# avr910_bluetooth.net
KiCad netlist of a schematic drawn in Altium Designer
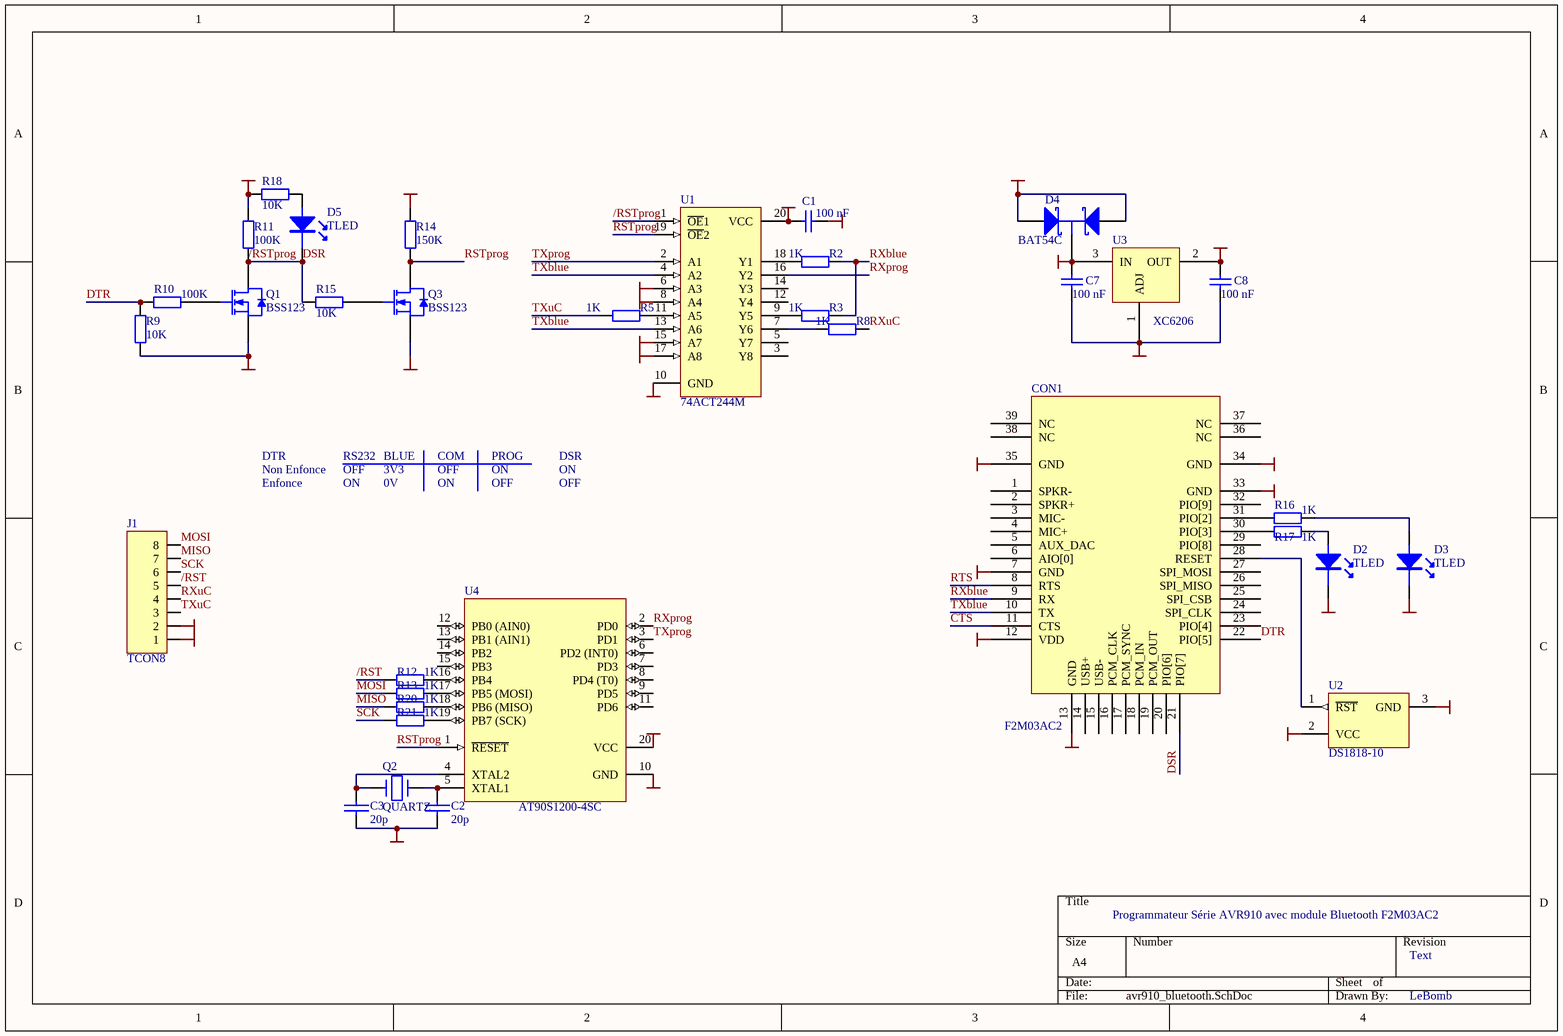
[diagram p0: avr910_bluetooth.SchDoc]

(export (version "E")
  (design (tool "Eeschema 10.0.6"))
  (components
    (comp (ref "C1")
      (value "100 nF")
      (footprint "0805")
      (description "Capacitor")
      (fields (field (name "Comment") "Cap") (field (name "PUBLISHER") "Altium Limited"))
      (libsource (lib "Miscellaneous Devices") (part "Cap"))
    )
    (comp (ref "C2") (value "20p") (footprint "0805") (libsource (lib "*") (part "CONDO")))
    (comp (ref "C3") (value "20p") (footprint "0805") (libsource (lib "*") (part "CONDO")))
    (comp (ref "C7")
      (value "100 nF")
      (footprint "0805")
      (description "Capacitor")
      (fields (field (name "Comment") "Cap") (field (name "PUBLISHER") "Altium Limited"))
      (libsource (lib "Miscellaneous Devices") (part "Cap"))
    )
    (comp (ref "C8")
      (value "100 nF")
      (footprint "0805")
      (description "Capacitor")
      (fields (field (name "Comment") "Cap") (field (name "PUBLISHER") "Altium Limited"))
      (libsource (lib "Miscellaneous Devices") (part "Cap"))
    )
    (comp (ref "CON1")
      (value "F2M03AC2")
      (footprint "F2M03AC2_conn")
      (libsource (lib "lebomb") (part "F2M03AC2"))
    )
    (comp (ref "D2") (value "TLED") (footprint "0805") (libsource (lib "ROB03") (part "TLED")))
    (comp (ref "D3") (value "TLED") (footprint "0805") (libsource (lib "ROB03") (part "TLED")))
    (comp (ref "D4")
      (value "BAT54C")
      (footprint "SOT23")
      (description "Schottky Barrier Double Diode")
      (fields (field (name "PUBLISHER") "Altium Limited"))
      (libsource (lib "Philips Discrete Diode - Schottky") (part "BAT54C"))
    )
    (comp (ref "D5") (value "TLED") (footprint "0805") (libsource (lib "ROB03") (part "TLED")))
    (comp (ref "J1") (value "TCON8") (footprint "TSIP8") (libsource (lib "ROB04") (part "TCON8")))
    (comp (ref "Q1")
      (value "BSS123")
      (footprint "SOT23")
      (description "N-channel Enhancement Mode Vertical D-MOSFET")
      (fields (field (name "PUBLISHER") "Altium Limited"))
      (libsource (lib "Philips Discrete MOSFET - Low Power") (part "BSS123"))
    )
    (comp (ref "Q2") (value "QUARTZ") (footprint "XTAL1") (libsource (lib "*") (part "QUARTZ")))
    (comp (ref "Q3")
      (value "BSS123")
      (footprint "SOT23")
      (description "N-channel Enhancement Mode Vertical D-MOSFET")
      (fields (field (name "PUBLISHER") "Altium Limited"))
      (libsource (lib "Philips Discrete MOSFET - Low Power") (part "BSS123"))
    )
    (comp (ref "R2")
      (value "1K")
      (footprint "0805")
      (description "Resistor")
      (fields (field (name "Comment") "Res2") (field (name "PUBLISHER") "Altium Limited"))
      (libsource (lib "Miscellaneous Devices") (part "Res2"))
    )
    (comp (ref "R3")
      (value "1K")
      (footprint "0805")
      (description "Resistor")
      (fields (field (name "Comment") "Res2") (field (name "PUBLISHER") "Altium Limited"))
      (libsource (lib "Miscellaneous Devices") (part "Res2"))
    )
    (comp (ref "R5")
      (value "1K")
      (footprint "0805")
      (description "Resistor")
      (fields (field (name "Comment") "Res2") (field (name "PUBLISHER") "Altium Limited"))
      (libsource (lib "Miscellaneous Devices") (part "Res2"))
    )
    (comp (ref "R8")
      (value "1K")
      (footprint "0805")
      (description "Resistor")
      (fields (field (name "Comment") "Res2") (field (name "PUBLISHER") "Altium Limited"))
      (libsource (lib "Miscellaneous Devices") (part "Res2"))
    )
    (comp (ref "R9")
      (value "10K")
      (footprint "0805")
      (description "Resistor")
      (fields (field (name "Comment") "Res2") (field (name "PUBLISHER") "Altium Limited"))
      (libsource (lib "") (part "Res2_1"))
    )
    (comp (ref "R10")
      (value "100K")
      (footprint "0805")
      (description "Resistor")
      (fields (field (name "Comment") "Res2") (field (name "PUBLISHER") "Altium Limited"))
      (libsource (lib "Miscellaneous Devices") (part "Res2"))
    )
    (comp (ref "R11")
      (value "100K")
      (footprint "0805")
      (description "Resistor")
      (fields (field (name "Comment") "Res2") (field (name "PUBLISHER") "Altium Limited"))
      (libsource (lib "") (part "Res2_1"))
    )
    (comp (ref "R12")
      (value "1K")
      (footprint "0805")
      (description "Resistor")
      (fields (field (name "Comment") "Res2") (field (name "PUBLISHER") "Altium Limited"))
      (libsource (lib "") (part "Res2_2"))
    )
    (comp (ref "R13")
      (value "1K")
      (footprint "0805")
      (description "Resistor")
      (fields (field (name "Comment") "Res2") (field (name "PUBLISHER") "Altium Limited"))
      (libsource (lib "") (part "Res2_2"))
    )
    (comp (ref "R14")
      (value "150K")
      (footprint "0805")
      (description "Resistor")
      (fields (field (name "Comment") "Res2") (field (name "PUBLISHER") "Altium Limited"))
      (libsource (lib "") (part "Res2_1"))
    )
    (comp (ref "R15")
      (value "10K")
      (footprint "0805")
      (description "Resistor")
      (fields (field (name "Comment") "Res2") (field (name "PUBLISHER") "Altium Limited"))
      (libsource (lib "") (part "Res2_2"))
    )
    (comp (ref "R16")
      (value "1K")
      (footprint "0805")
      (description "Resistor")
      (fields (field (name "Comment") "Res2") (field (name "PUBLISHER") "Altium Limited"))
      (libsource (lib "Miscellaneous Devices") (part "Res2"))
    )
    (comp (ref "R17")
      (value "1K")
      (footprint "0805")
      (description "Resistor")
      (fields (field (name "Comment") "Res2") (field (name "PUBLISHER") "Altium Limited"))
      (libsource (lib "Miscellaneous Devices") (part "Res2"))
    )
    (comp (ref "R18")
      (value "10K")
      (footprint "0805")
      (description "Resistor")
      (fields (field (name "Comment") "Res2") (field (name "PUBLISHER") "Altium Limited"))
      (libsource (lib "") (part "Res2_2"))
    )
    (comp (ref "R20")
      (value "1K")
      (footprint "0805")
      (description "Resistor")
      (fields (field (name "Comment") "Res2") (field (name "PUBLISHER") "Altium Limited"))
      (libsource (lib "") (part "Res2_2"))
    )
    (comp (ref "R21")
      (value "1K")
      (footprint "0805")
      (description "Resistor")
      (fields (field (name "Comment") "Res2") (field (name "PUBLISHER") "Altium Limited"))
      (libsource (lib "") (part "Res2_2"))
    )
    (comp (ref "U1")
      (value "74ACT244M")
      (footprint "SO20")
      (description "Octal Bus Buffer with 3 State Outputs (Non Inverted)")
      (fields (field (name "PUBLISHER") "Altium Limited"))
      (libsource (lib "ST Logic Buffer Line Driver") (part "74ACT244M"))
    )
    (comp (ref "U2")
      (value "DS1818-10")
      (footprint "SOT-23")
      (description "3.3V EconoReset with Pushbutton")
      (fields (field (name "PUBLISHER") "Altium Limited"))
      (libsource (lib "Dallas Power Mgt Voltage Detector") (part "DS1818-10"))
    )
    (comp (ref "U3") (value "XC6206") (footprint "sot-23") (libsource (lib "ROB04") (part "LM317")))
    (comp (ref "U4")
      (value "AT90S1200-4SC")
      (footprint "20S")
      (description "8-Bit AVR Microcontroller with 1K Byte of In-System Programmable Flash Memory")
      (fields (field (name "PUBLISHER") "Altium Limited"))
      (libsource (lib "Atmel Microcontroller 8-Bit AVR") (part "AT90S1200-4SC"))
    )
  )
  (nets
    (net (code "1") (name "/CTS") (class "Default")
      (node (ref "CON1") (pin "11") (pinfunction "CTS_11") (pintype "passive"))
    )
    (net (code "2") (name "/DSR") (class "Default")
      (node (ref "CON1") (pin "21") (pinfunction "PIO[7]_21") (pintype "passive"))
      (node (ref "D5") (pin "2") (pinfunction "2_2") (pintype "passive"))
      (node (ref "Q1") (pin "3") (pinfunction "D_3") (pintype "passive"))
      (node (ref "R11") (pin "1") (pinfunction "1_1") (pintype "passive"))
      (node (ref "R15") (pin "2") (pinfunction "2_2") (pintype "passive"))
      (node (ref "U1") (pin "1") (pinfunction "~{OE}1_1") (pintype "input"))
    )
    (net (code "3") (name "/DTR") (class "Default")
      (node (ref "CON1") (pin "22") (pinfunction "PIO[5]_22") (pintype "passive"))
      (node (ref "R10") (pin "1") (pinfunction "1_1") (pintype "passive"))
      (node (ref "R9") (pin "2") (pinfunction "2_2") (pintype "passive"))
    )
    (net (code "4") (name "/MISO") (class "Default")
      (node (ref "J1") (pin "7") (pinfunction "7_7") (pintype "passive"))
      (node (ref "R20") (pin "2") (pinfunction "2_2") (pintype "passive"))
    )
    (net (code "5") (name "/MOSI") (class "Default")
      (node (ref "J1") (pin "8") (pinfunction "8_8") (pintype "passive"))
      (node (ref "R13") (pin "2") (pinfunction "2_2") (pintype "passive"))
    )
    (net (code "6") (name "/RSTprog") (class "Default")
      (node (ref "Q3") (pin "3") (pinfunction "D_3") (pintype "passive"))
      (node (ref "R14") (pin "1") (pinfunction "1_1") (pintype "passive"))
      (node (ref "U1") (pin "19") (pinfunction "~{OE}2_19") (pintype "input"))
      (node (ref "U4") (pin "1") (pinfunction "~{RESET}_1") (pintype "input"))
    )
    (net (code "7") (name "/RTS") (class "Default")
      (node (ref "CON1") (pin "8") (pinfunction "RTS_8") (pintype "passive"))
    )
    (net (code "8") (name "/RXblue") (class "Default")
      (node (ref "CON1") (pin "9") (pinfunction "RX_9") (pintype "passive"))
      (node (ref "R2") (pin "2") (pinfunction "2_2") (pintype "passive"))
      (node (ref "R3") (pin "2") (pinfunction "2_2") (pintype "passive"))
    )
    (net (code "9") (name "/RXprog") (class "Default")
      (node (ref "U1") (pin "16") (pinfunction "Y2_16") (pintype "tri_state"))
      (node (ref "U4") (pin "2") (pinfunction "PD0_2") (pintype "bidirectional"))
    )
    (net (code "10") (name "/RXuC") (class "Default")
      (node (ref "J1") (pin "4") (pinfunction "4_4") (pintype "passive"))
      (node (ref "R8") (pin "2") (pinfunction "2_2") (pintype "passive"))
    )
    (net (code "11") (name "/SCK") (class "Default")
      (node (ref "J1") (pin "6") (pinfunction "6_6") (pintype "passive"))
      (node (ref "R21") (pin "2") (pinfunction "2_2") (pintype "passive"))
    )
    (net (code "12") (name "/TXblue") (class "Default")
      (node (ref "CON1") (pin "10") (pinfunction "TX_10") (pintype "passive"))
      (node (ref "U1") (pin "13") (pinfunction "A6_13") (pintype "input"))
      (node (ref "U1") (pin "4") (pinfunction "A2_4") (pintype "input"))
    )
    (net (code "13") (name "/TXprog") (class "Default")
      (node (ref "U1") (pin "2") (pinfunction "A1_2") (pintype "input"))
      (node (ref "U4") (pin "3") (pinfunction "PD1_3") (pintype "bidirectional"))
    )
    (net (code "14") (name "/TXuC") (class "Default")
      (node (ref "J1") (pin "3") (pinfunction "3_3") (pintype "passive"))
      (node (ref "R5") (pin "1") (pinfunction "1_1") (pintype "passive"))
    )
    (net (code "15") (name "/{slash}RST") (class "Default")
      (node (ref "J1") (pin "5") (pinfunction "5_5") (pintype "passive"))
      (node (ref "R12") (pin "2") (pinfunction "2_2") (pintype "passive"))
    )
    (net (code "16") (name "3V3") (class "Default")
      (node (ref "C1") (pin "1") (pinfunction "1_1") (pintype "passive"))
      (node (ref "C8") (pin "2") (pinfunction "2_2") (pintype "passive"))
      (node (ref "CON1") (pin "12") (pinfunction "VDD_12") (pintype "passive"))
      (node (ref "R11") (pin "2") (pinfunction "2_2") (pintype "passive"))
      (node (ref "R14") (pin "2") (pinfunction "2_2") (pintype "passive"))
      (node (ref "R18") (pin "2") (pinfunction "2_2") (pintype "passive"))
      (node (ref "U1") (pin "20") (pinfunction "VCC_20") (pintype "power_in"))
      (node (ref "U2") (pin "2") (pinfunction "VCC_2") (pintype "power_in"))
      (node (ref "U3") (pin "2") (pinfunction "OUT_2") (pintype "passive"))
    )
    (net (code "17") (name "5V") (class "Default")
      (node (ref "C7") (pin "2") (pinfunction "2_2") (pintype "passive"))
      (node (ref "D4") (pin "3") (pinfunction "K_3") (pintype "passive"))
      (node (ref "U3") (pin "3") (pinfunction "IN_3") (pintype "passive"))
      (node (ref "U4") (pin "20") (pinfunction "VCC_20") (pintype "power_in"))
    )
    (net (code "18") (name "GND") (class "Default")
      (node (ref "C1") (pin "2") (pinfunction "2_2") (pintype "passive"))
      (node (ref "C2") (pin "2") (pintype "passive"))
      (node (ref "C3") (pin "2") (pintype "passive"))
      (node (ref "C7") (pin "1") (pinfunction "1_1") (pintype "passive"))
      (node (ref "C8") (pin "1") (pinfunction "1_1") (pintype "passive"))
      (node (ref "CON1") (pin "13") (pinfunction "GND_13") (pintype "passive"))
      (node (ref "CON1") (pin "33") (pinfunction "GND_33") (pintype "passive"))
      (node (ref "CON1") (pin "34") (pinfunction "GND_34") (pintype "passive"))
      (node (ref "CON1") (pin "35") (pinfunction "GND_35") (pintype "passive"))
      (node (ref "CON1") (pin "7") (pinfunction "GND_7") (pintype "passive"))
      (node (ref "D2") (pin "2") (pinfunction "2_2") (pintype "passive"))
      (node (ref "D3") (pin "2") (pinfunction "2_2") (pintype "passive"))
      (node (ref "J1") (pin "2") (pinfunction "2_2") (pintype "passive"))
      (node (ref "Q1") (pin "2") (pinfunction "S_2") (pintype "passive"))
      (node (ref "Q3") (pin "2") (pinfunction "S_2") (pintype "passive"))
      (node (ref "R9") (pin "1") (pinfunction "1_1") (pintype "passive"))
      (node (ref "U1") (pin "10") (pinfunction "GND_10") (pintype "power_in"))
      (node (ref "U1") (pin "15") (pinfunction "A7_15") (pintype "input"))
      (node (ref "U1") (pin "17") (pinfunction "A8_17") (pintype "input"))
      (node (ref "U1") (pin "6") (pinfunction "A3_6") (pintype "input"))
      (node (ref "U1") (pin "8") (pinfunction "A4_8") (pintype "input"))
      (node (ref "U2") (pin "3") (pinfunction "GND_3") (pintype "power_in"))
      (node (ref "U3") (pin "1") (pinfunction "ADJ_1") (pintype "passive"))
      (node (ref "U4") (pin "10") (pinfunction "GND_10") (pintype "power_in"))
    )
    (net (code "19") (name "Net-(CON1-PIO[2])") (class "Default")
      (node (ref "CON1") (pin "31") (pinfunction "PIO[2]_31") (pintype "passive"))
      (node (ref "R16") (pin "1") (pinfunction "1_1") (pintype "passive"))
    )
    (net (code "20") (name "Net-(CON1-PIO[3])") (class "Default")
      (node (ref "CON1") (pin "30") (pinfunction "PIO[3]_30") (pintype "passive"))
      (node (ref "R17") (pin "1") (pinfunction "1_1") (pintype "passive"))
    )
    (net (code "21") (name "Net-(CON1-RESET)") (class "Default")
      (node (ref "CON1") (pin "28") (pinfunction "RESET_28") (pintype "passive"))
      (node (ref "U2") (pin "1") (pinfunction "~{RST}_1") (pintype "output"))
    )
    (net (code "22") (name "Net-(D2-Pad1)") (class "Default")
      (node (ref "D2") (pin "1") (pinfunction "1_1") (pintype "passive"))
      (node (ref "R17") (pin "2") (pinfunction "2_2") (pintype "passive"))
    )
    (net (code "23") (name "Net-(D3-Pad1)") (class "Default")
      (node (ref "D3") (pin "1") (pinfunction "1_1") (pintype "passive"))
      (node (ref "R16") (pin "2") (pinfunction "2_2") (pintype "passive"))
    )
    (net (code "24") (name "Net-(D5-Pad1)") (class "Default")
      (node (ref "D5") (pin "1") (pinfunction "1_1") (pintype "passive"))
      (node (ref "R18") (pin "1") (pinfunction "1_1") (pintype "passive"))
    )
    (net (code "25") (name "Net-(Q1-G)") (class "Default")
      (node (ref "Q1") (pin "1") (pinfunction "G_1") (pintype "passive"))
      (node (ref "R10") (pin "2") (pinfunction "2_2") (pintype "passive"))
    )
    (net (code "26") (name "Net-(Q3-G)") (class "Default")
      (node (ref "Q3") (pin "1") (pinfunction "G_1") (pintype "passive"))
      (node (ref "R15") (pin "1") (pinfunction "1_1") (pintype "passive"))
    )
    (net (code "27") (name "Net-(U1-A5)") (class "Default")
      (node (ref "R5") (pin "2") (pinfunction "2_2") (pintype "passive"))
      (node (ref "U1") (pin "11") (pinfunction "A5_11") (pintype "input"))
    )
    (net (code "28") (name "Net-(U1-Y1)") (class "Default")
      (node (ref "R2") (pin "1") (pinfunction "1_1") (pintype "passive"))
      (node (ref "U1") (pin "18") (pinfunction "Y1_18") (pintype "tri_state"))
    )
    (net (code "29") (name "Net-(U1-Y5)") (class "Default")
      (node (ref "R3") (pin "1") (pinfunction "1_1") (pintype "passive"))
      (node (ref "U1") (pin "9") (pinfunction "Y5_9") (pintype "tri_state"))
    )
    (net (code "30") (name "Net-(U1-Y6)") (class "Default")
      (node (ref "R8") (pin "1") (pinfunction "1_1") (pintype "passive"))
      (node (ref "U1") (pin "7") (pinfunction "Y6_7") (pintype "tri_state"))
    )
    (net (code "31") (name "Net-(U4-PB4)") (class "Default")
      (node (ref "R12") (pin "1") (pinfunction "1_1") (pintype "passive"))
      (node (ref "U4") (pin "16") (pinfunction "PB4_16") (pintype "bidirectional"))
    )
    (net (code "32") (name "Net-(U4-PB5_(MOSI))") (class "Default")
      (node (ref "R13") (pin "1") (pinfunction "1_1") (pintype "passive"))
      (node (ref "U4") (pin "17") (pinfunction "PB5_(MOSI)_17") (pintype "bidirectional"))
    )
    (net (code "33") (name "Net-(U4-PB6_(MISO))") (class "Default")
      (node (ref "R20") (pin "1") (pinfunction "1_1") (pintype "passive"))
      (node (ref "U4") (pin "18") (pinfunction "PB6_(MISO)_18") (pintype "bidirectional"))
    )
    (net (code "34") (name "Net-(U4-PB7_(SCK))") (class "Default")
      (node (ref "R21") (pin "1") (pinfunction "1_1") (pintype "passive"))
      (node (ref "U4") (pin "19") (pinfunction "PB7_(SCK)_19") (pintype "bidirectional"))
    )
    (net (code "35") (name "Net-(U4-XTAL1)") (class "Default")
      (node (ref "C2") (pin "1") (pintype "passive"))
      (node (ref "Q2") (pin "2") (pintype "passive"))
      (node (ref "U4") (pin "5") (pinfunction "XTAL1_5") (pintype "passive"))
    )
    (net (code "36") (name "Net-(U4-XTAL2)") (class "Default")
      (node (ref "C3") (pin "1") (pintype "passive"))
      (node (ref "Q2") (pin "1") (pintype "passive"))
      (node (ref "U4") (pin "4") (pinfunction "XTAL2_4") (pintype "passive"))
    )
    (net (code "37") (name "VCC") (class "Default")
      (node (ref "D4") (pin "1") (pinfunction "A1_1") (pintype "passive"))
      (node (ref "D4") (pin "2") (pinfunction "A2_2") (pintype "passive"))
      (node (ref "J1") (pin "1") (pinfunction "1_1") (pintype "passive"))
    )
    (net (code "38") (name "unconnected-(CON1-AIO[0]-Pad6)") (class "Default")
      (node (ref "CON1") (pin "6") (pinfunction "AIO[0]_6") (pintype "passive"))
    )
    (net (code "39") (name "unconnected-(CON1-AUX_DAC-Pad5)") (class "Default")
      (node (ref "CON1") (pin "5") (pinfunction "AUX_DAC_5") (pintype "passive"))
    )
    (net (code "40") (name "unconnected-(CON1-MIC+-Pad4)") (class "Default")
      (node (ref "CON1") (pin "4") (pinfunction "MIC+_4") (pintype "passive"))
    )
    (net (code "41") (name "unconnected-(CON1-MIC--Pad3)") (class "Default")
      (node (ref "CON1") (pin "3") (pinfunction "MIC-_3") (pintype "passive"))
    )
    (net (code "42") (name "unconnected-(CON1-NC-Pad36)") (class "Default")
      (node (ref "CON1") (pin "36") (pinfunction "NC_36") (pintype "passive"))
    )
    (net (code "43") (name "unconnected-(CON1-NC-Pad37)") (class "Default")
      (node (ref "CON1") (pin "37") (pinfunction "NC_37") (pintype "passive"))
    )
    (net (code "44") (name "unconnected-(CON1-NC-Pad38)") (class "Default")
      (node (ref "CON1") (pin "38") (pinfunction "NC_38") (pintype "passive"))
    )
    (net (code "45") (name "unconnected-(CON1-NC-Pad39)") (class "Default")
      (node (ref "CON1") (pin "39") (pinfunction "NC_39") (pintype "passive"))
    )
    (net (code "46") (name "unconnected-(CON1-PCM_CLK-Pad16)") (class "Default")
      (node (ref "CON1") (pin "16") (pinfunction "PCM_CLK_16") (pintype "passive"))
    )
    (net (code "47") (name "unconnected-(CON1-PCM_IN-Pad18)") (class "Default")
      (node (ref "CON1") (pin "18") (pinfunction "PCM_IN_18") (pintype "passive"))
    )
    (net (code "48") (name "unconnected-(CON1-PCM_OUT-Pad19)") (class "Default")
      (node (ref "CON1") (pin "19") (pinfunction "PCM_OUT_19") (pintype "passive"))
    )
    (net (code "49") (name "unconnected-(CON1-PCM_SYNC-Pad17)") (class "Default")
      (node (ref "CON1") (pin "17") (pinfunction "PCM_SYNC_17") (pintype "passive"))
    )
    (net (code "50") (name "unconnected-(CON1-PIO[4]-Pad23)") (class "Default")
      (node (ref "CON1") (pin "23") (pinfunction "PIO[4]_23") (pintype "passive"))
    )
    (net (code "51") (name "unconnected-(CON1-PIO[6]-Pad20)") (class "Default")
      (node (ref "CON1") (pin "20") (pinfunction "PIO[6]_20") (pintype "passive"))
    )
    (net (code "52") (name "unconnected-(CON1-PIO[8]-Pad29)") (class "Default")
      (node (ref "CON1") (pin "29") (pinfunction "PIO[8]_29") (pintype "passive"))
    )
    (net (code "53") (name "unconnected-(CON1-PIO[9]-Pad32)") (class "Default")
      (node (ref "CON1") (pin "32") (pinfunction "PIO[9]_32") (pintype "passive"))
    )
    (net (code "54") (name "unconnected-(CON1-SPI_CLK-Pad24)") (class "Default")
      (node (ref "CON1") (pin "24") (pinfunction "SPI_CLK_24") (pintype "passive"))
    )
    (net (code "55") (name "unconnected-(CON1-SPI_CSB-Pad25)") (class "Default")
      (node (ref "CON1") (pin "25") (pinfunction "SPI_CSB_25") (pintype "passive"))
    )
    (net (code "56") (name "unconnected-(CON1-SPI_MISO-Pad26)") (class "Default")
      (node (ref "CON1") (pin "26") (pinfunction "SPI_MISO_26") (pintype "passive"))
    )
    (net (code "57") (name "unconnected-(CON1-SPI_MOSI-Pad27)") (class "Default")
      (node (ref "CON1") (pin "27") (pinfunction "SPI_MOSI_27") (pintype "passive"))
    )
    (net (code "58") (name "unconnected-(CON1-SPKR+-Pad2)") (class "Default")
      (node (ref "CON1") (pin "2") (pinfunction "SPKR+_2") (pintype "passive"))
    )
    (net (code "59") (name "unconnected-(CON1-SPKR--Pad1)") (class "Default")
      (node (ref "CON1") (pin "1") (pinfunction "SPKR-_1") (pintype "passive"))
    )
    (net (code "60") (name "unconnected-(CON1-USB+-Pad14)") (class "Default")
      (node (ref "CON1") (pin "14") (pinfunction "USB+_14") (pintype "passive"))
    )
    (net (code "61") (name "unconnected-(CON1-USB--Pad15)") (class "Default")
      (node (ref "CON1") (pin "15") (pinfunction "USB-_15") (pintype "passive"))
    )
    (net (code "62") (name "unconnected-(U1-Y3-Pad14)") (class "Default")
      (node (ref "U1") (pin "14") (pinfunction "Y3_14") (pintype "tri_state"))
    )
    (net (code "63") (name "unconnected-(U1-Y4-Pad12)") (class "Default")
      (node (ref "U1") (pin "12") (pinfunction "Y4_12") (pintype "tri_state"))
    )
    (net (code "64") (name "unconnected-(U1-Y7-Pad5)") (class "Default")
      (node (ref "U1") (pin "5") (pinfunction "Y7_5") (pintype "tri_state"))
    )
    (net (code "65") (name "unconnected-(U1-Y8-Pad3)") (class "Default")
      (node (ref "U1") (pin "3") (pinfunction "Y8_3") (pintype "tri_state"))
    )
    (net (code "66") (name "unconnected-(U4-PB0_(AIN0)-Pad12)") (class "Default")
      (node (ref "U4") (pin "12") (pinfunction "PB0_(AIN0)_12") (pintype "bidirectional"))
    )
    (net (code "67") (name "unconnected-(U4-PB1_(AIN1)-Pad13)") (class "Default")
      (node (ref "U4") (pin "13") (pinfunction "PB1_(AIN1)_13") (pintype "bidirectional"))
    )
    (net (code "68") (name "unconnected-(U4-PB2-Pad14)") (class "Default")
      (node (ref "U4") (pin "14") (pinfunction "PB2_14") (pintype "bidirectional"))
    )
    (net (code "69") (name "unconnected-(U4-PB3-Pad15)") (class "Default")
      (node (ref "U4") (pin "15") (pinfunction "PB3_15") (pintype "bidirectional"))
    )
    (net (code "70") (name "unconnected-(U4-PD2_(INT0)-Pad6)") (class "Default")
      (node (ref "U4") (pin "6") (pinfunction "PD2_(INT0)_6") (pintype "bidirectional"))
    )
    (net (code "71") (name "unconnected-(U4-PD3-Pad7)") (class "Default")
      (node (ref "U4") (pin "7") (pinfunction "PD3_7") (pintype "bidirectional"))
    )
    (net (code "72") (name "unconnected-(U4-PD4_(T0)-Pad8)") (class "Default")
      (node (ref "U4") (pin "8") (pinfunction "PD4_(T0)_8") (pintype "bidirectional"))
    )
    (net (code "73") (name "unconnected-(U4-PD5-Pad9)") (class "Default")
      (node (ref "U4") (pin "9") (pinfunction "PD5_9") (pintype "bidirectional"))
    )
    (net (code "74") (name "unconnected-(U4-PD6-Pad11)") (class "Default")
      (node (ref "U4") (pin "11") (pinfunction "PD6_11") (pintype "bidirectional"))
    )
  )
)
